# ProPrj_VI_sense_2025-01-02.net
KiCad netlist of a schematic drawn in EasyEDA Pro
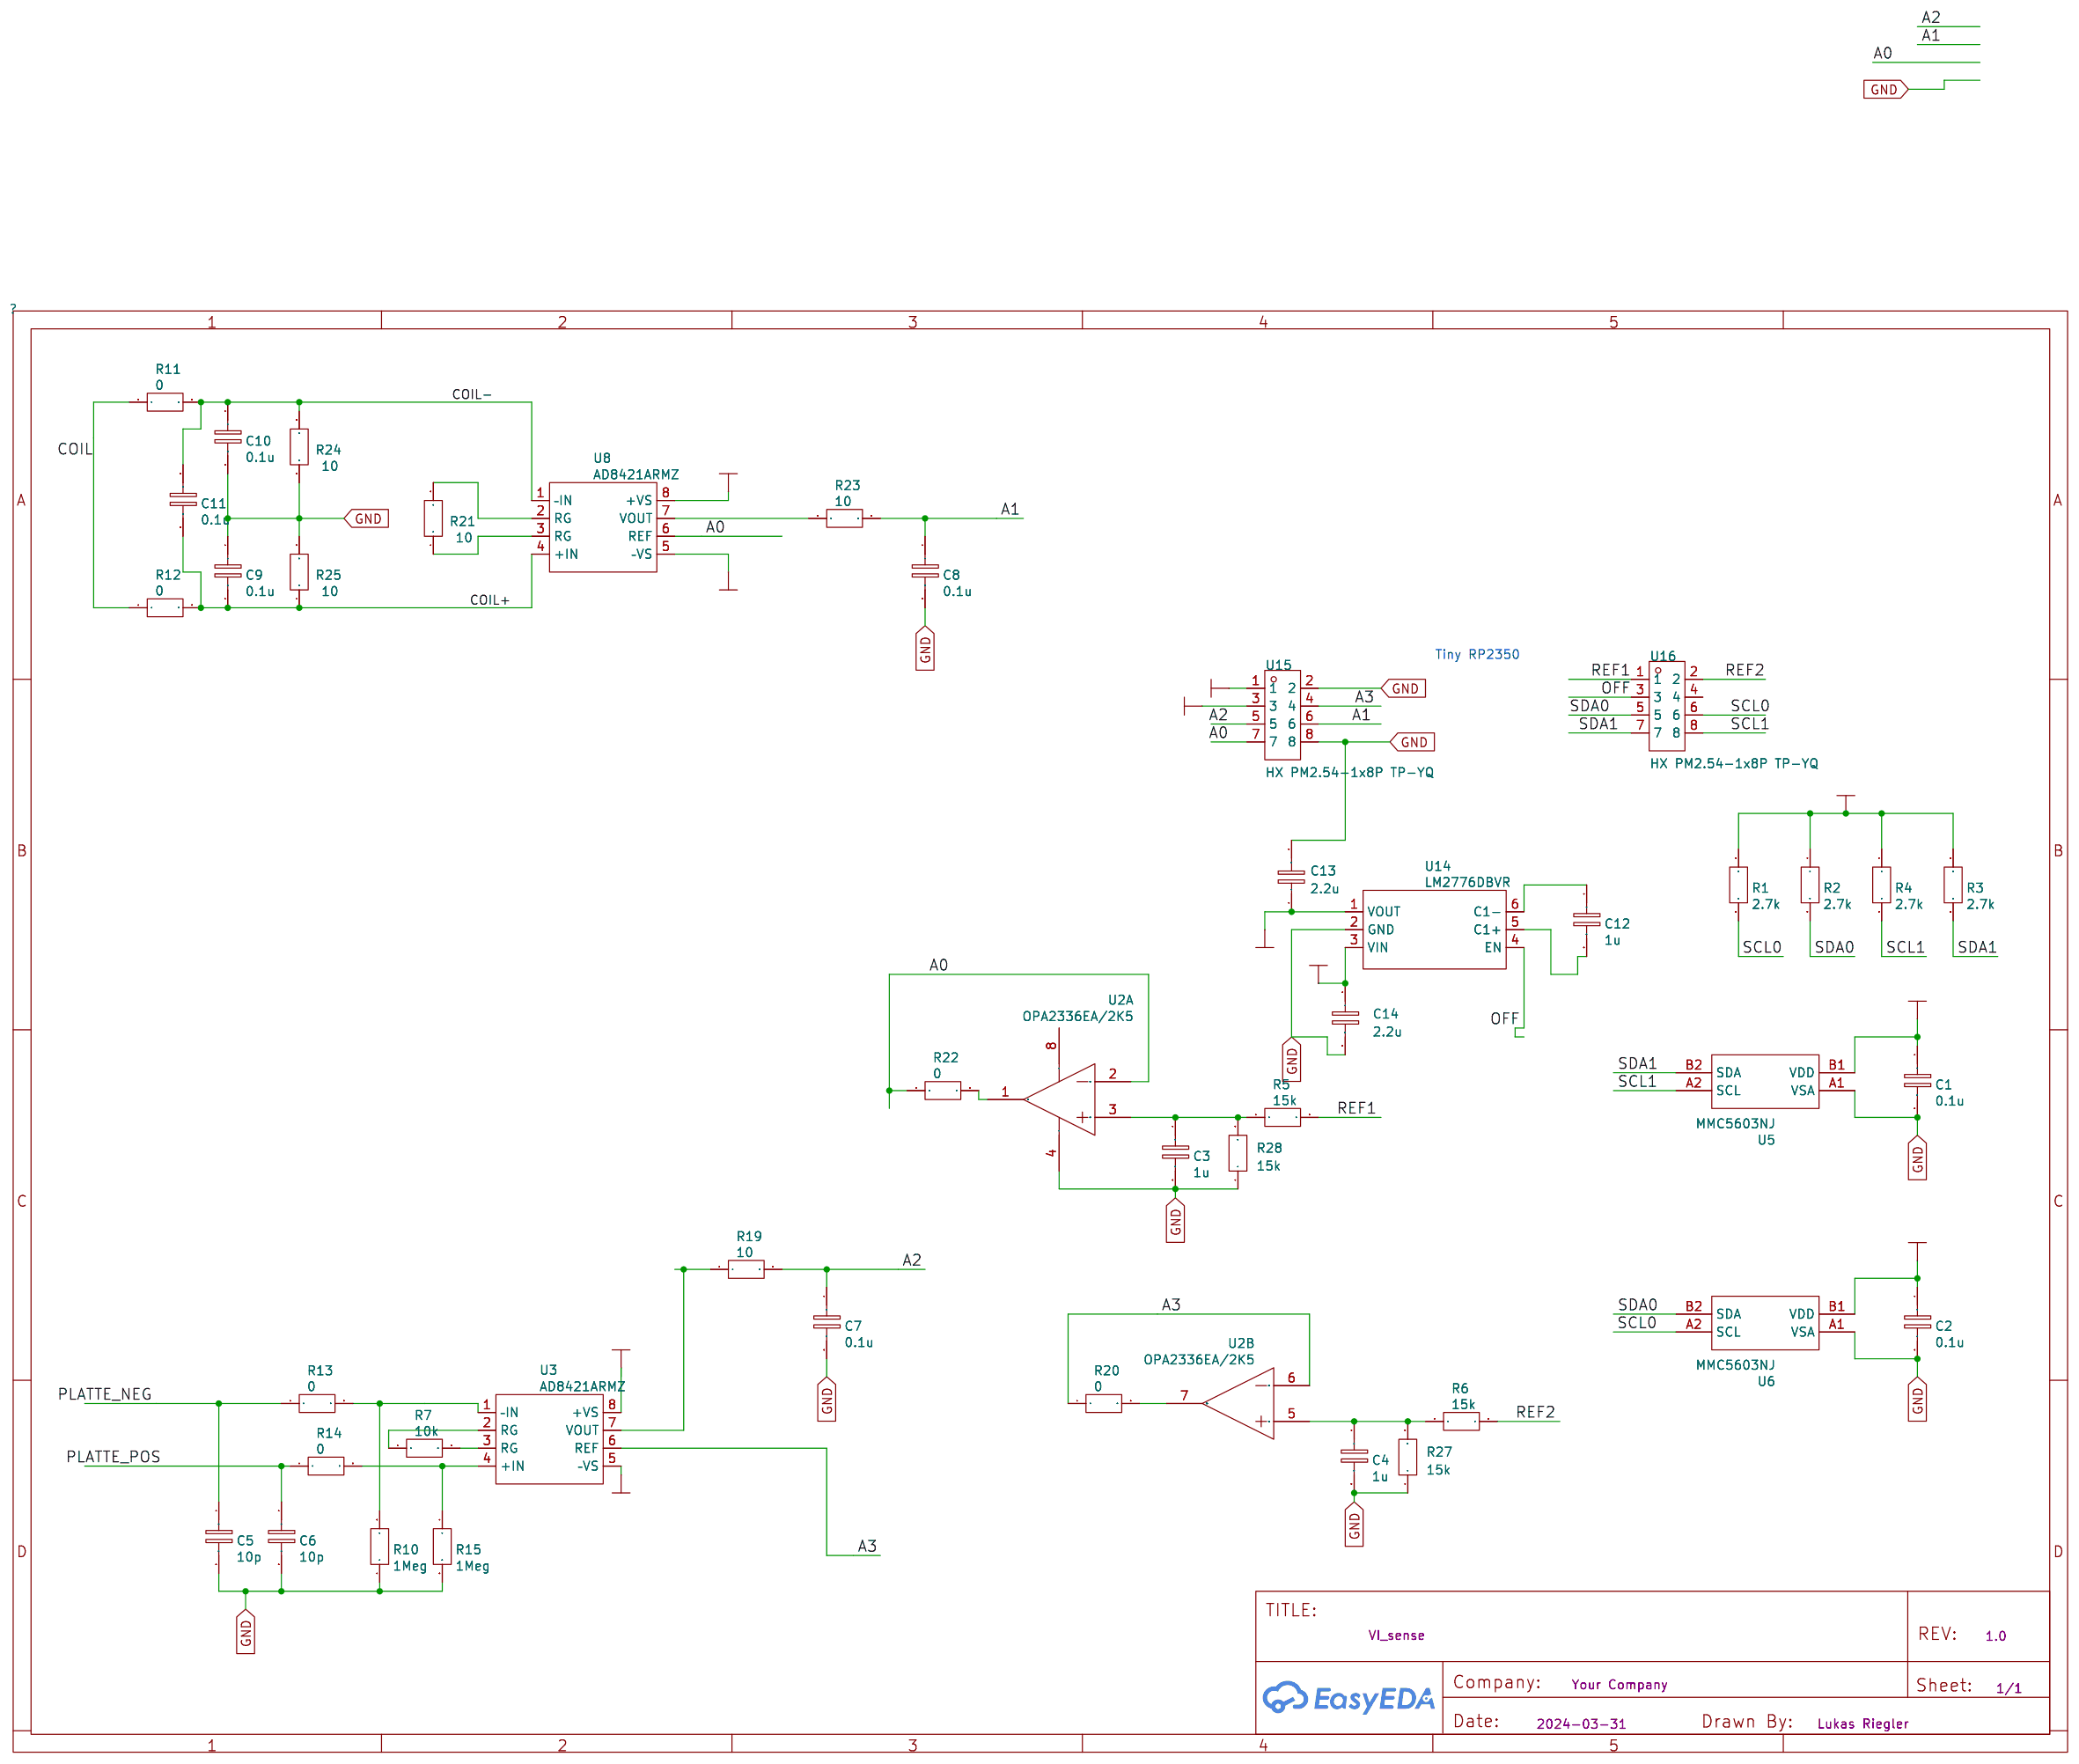
[diagram p0: schematic sheet]

(export (version "E")
  (design (tool "Eeschema 10.0.6"))
  (components
    (comp (ref "C1")
      (value "0.1u")
      (footprint "easyedapro:C0603")
      (libsource (lib "easyedapro") (part "0.1u"))
    )
    (comp (ref "C2")
      (value "0.1u")
      (footprint "easyedapro:C0603")
      (libsource (lib "easyedapro") (part "0.1u"))
    )
    (comp (ref "C3") (value "1u") (footprint "easyedapro:C0603") (libsource (lib "easyedapro") (part "1u")))
    (comp (ref "C4") (value "1u") (footprint "easyedapro:C0603") (libsource (lib "easyedapro") (part "1u")))
    (comp (ref "C5") (value "10p") (footprint "easyedapro:C0603") (libsource (lib "easyedapro") (part "10p")))
    (comp (ref "C6") (value "10p") (footprint "easyedapro:C0603") (libsource (lib "easyedapro") (part "10p")))
    (comp (ref "C7")
      (value "0.1u")
      (footprint "easyedapro:C0603")
      (libsource (lib "easyedapro") (part "0.1u"))
    )
    (comp (ref "C8")
      (value "0.1u")
      (footprint "easyedapro:C0603")
      (libsource (lib "easyedapro") (part "0.1u"))
    )
    (comp (ref "C9")
      (value "0.1u")
      (footprint "easyedapro:C0603")
      (libsource (lib "easyedapro") (part "0.1u"))
    )
    (comp (ref "C10")
      (value "0.1u")
      (footprint "easyedapro:C0603")
      (libsource (lib "easyedapro") (part "0.1u"))
    )
    (comp (ref "C11")
      (value "0.1u")
      (footprint "easyedapro:C0603")
      (libsource (lib "easyedapro") (part "0.1u"))
    )
    (comp (ref "C12")
      (value "1u")
      (footprint "easyedapro:C0603")
      (libsource (lib "easyedapro") (part "0.1u"))
    )
    (comp (ref "C13")
      (value "2.2u")
      (footprint "easyedapro:C0603")
      (libsource (lib "easyedapro") (part "0.1u"))
    )
    (comp (ref "C14")
      (value "2.2u")
      (footprint "easyedapro:C0603")
      (libsource (lib "easyedapro") (part "0.1u"))
    )
    (comp (ref "R1")
      (value "2.7k")
      (footprint "easyedapro:R0603")
      (libsource (lib "easyedapro") (part "2.7k"))
    )
    (comp (ref "R2")
      (value "2.7k")
      (footprint "easyedapro:R0603")
      (libsource (lib "easyedapro") (part "2.7k"))
    )
    (comp (ref "R3")
      (value "2.7k")
      (footprint "easyedapro:R0603")
      (libsource (lib "easyedapro") (part "2.7k"))
    )
    (comp (ref "R4")
      (value "2.7k")
      (footprint "easyedapro:R0603")
      (libsource (lib "easyedapro") (part "2.7k"))
    )
    (comp (ref "R5") (value "15k") (footprint "easyedapro:R0603") (libsource (lib "easyedapro") (part "15k")))
    (comp (ref "R6") (value "15k") (footprint "easyedapro:R0603") (libsource (lib "easyedapro") (part "15k")))
    (comp (ref "R7") (value "10k") (footprint "easyedapro:R0603") (libsource (lib "easyedapro") (part "10k")))
    (comp (ref "R10")
      (value "1Meg")
      (footprint "easyedapro:R0603")
      (libsource (lib "easyedapro") (part "1Meg"))
    )
    (comp (ref "R11") (value "0") (footprint "easyedapro:R0603") (libsource (lib "easyedapro") (part "0")))
    (comp (ref "R12") (value "0") (footprint "easyedapro:R0603") (libsource (lib "easyedapro") (part "0")))
    (comp (ref "R13") (value "0") (footprint "easyedapro:R0603") (libsource (lib "easyedapro") (part "0")))
    (comp (ref "R14") (value "0") (footprint "easyedapro:R0603") (libsource (lib "easyedapro") (part "0")))
    (comp (ref "R15")
      (value "1Meg")
      (footprint "easyedapro:R0603")
      (libsource (lib "easyedapro") (part "1Meg"))
    )
    (comp (ref "R19") (value "10") (footprint "easyedapro:R0603") (libsource (lib "easyedapro") (part "10")))
    (comp (ref "R20") (value "0") (footprint "easyedapro:R0603") (libsource (lib "easyedapro") (part "0")))
    (comp (ref "R21") (value "10") (footprint "easyedapro:R0603") (libsource (lib "easyedapro") (part "10")))
    (comp (ref "R22") (value "0") (footprint "easyedapro:R0603") (libsource (lib "easyedapro") (part "0")))
    (comp (ref "R23") (value "10") (footprint "easyedapro:R0603") (libsource (lib "easyedapro") (part "10")))
    (comp (ref "R24") (value "10") (footprint "easyedapro:R0603") (libsource (lib "easyedapro") (part "10")))
    (comp (ref "R25") (value "10") (footprint "easyedapro:R0603") (libsource (lib "easyedapro") (part "10")))
    (comp (ref "R27")
      (value "15k")
      (footprint "easyedapro:R0603")
      (libsource (lib "easyedapro") (part "15k"))
    )
    (comp (ref "R28")
      (value "15k")
      (footprint "easyedapro:R0603")
      (libsource (lib "easyedapro") (part "15k"))
    )
    (comp (ref "U2")
      (value "OPA2336EA/2K5")
      (footprint "easyedapro:VSSOP-8_L3.0-W3.0-P0.65-LS4.9-BL")
      (fields (field (name "Manufacturer") "TI(德州仪器)"))
      (libsource (lib "easyedapro") (part "OPA2336EA/2K5"))
    )
    (comp (ref "U3")
      (value "AD8421ARMZ")
      (footprint "easyedapro:MSOP-8_L3.0-W3.0-P0.65-LS4.9-BL")
      (fields (field (name "Manufacturer") "ADI(亚德诺)"))
      (libsource (lib "easyedapro") (part "AD8421ARMZ"))
    )
    (comp (ref "U5")
      (value "MMC5603NJ")
      (footprint "easyedapro:FLIPCHIP-4_L0.8-W0.8-R2-C2-P0.40-TL")
      (fields (field (name "Manufacturer") "MEMSIC(美新)"))
      (libsource (lib "easyedapro") (part "MMC5603NJ"))
    )
    (comp (ref "U6")
      (value "MMC5603NJ")
      (footprint "easyedapro:FLIPCHIP-4_L0.8-W0.8-R2-C2-P0.40-TL")
      (fields (field (name "Manufacturer") "MEMSIC(美新)"))
      (libsource (lib "easyedapro") (part "MMC5603NJ"))
    )
    (comp (ref "U8")
      (value "AD8421ARMZ")
      (footprint "easyedapro:MSOP-8_L3.0-W3.0-P0.65-LS4.9-BL")
      (fields (field (name "Manufacturer") "ADI(亚德诺)"))
      (libsource (lib "easyedapro") (part "AD8421ARMZ"))
    )
    (comp (ref "U14")
      (value "LM2776DBVR")
      (footprint "easyedapro:SOT-23-6_L2.9-W1.6-P0.95-LS2.8-BR")
      (fields (field (name "Manufacturer") "TI(德州仪器)"))
      (libsource (lib "easyedapro") (part "LM2776DBVR"))
    )
    (comp (ref "U15")
      (value "HX PM2.54-1x8P TP-YQ")
      (footprint "easyedapro:HDR-SMD_8P-P2.54-V-M-LS4.8_XKB_R1")
      (fields (field (name "Manufacturer") "hanxia(韩下)"))
      (libsource (lib "easyedapro") (part "HX PM2.54-1X8P TP-YQ"))
    )
    (comp (ref "U16")
      (value "HX PM2.54-1x8P TP-YQ")
      (footprint "easyedapro:HDR-SMD_8P-P2.54-V-M-LS4.8_XKB_R1")
      (fields (field (name "Manufacturer") "hanxia(韩下)"))
      (libsource (lib "easyedapro") (part "HX PM2.54-1X8P TP-YQ"))
    )
  )
  (nets
    (net (code "1") (name "+3.3V") (class "Default")
      (node (ref "C1") (pin "1") (pinfunction "1_1") (pintype "unspecified"))
      (node (ref "C2") (pin "1") (pinfunction "1_1") (pintype "unspecified"))
      (node (ref "R1") (pin "1") (pinfunction "1_1") (pintype "unspecified"))
      (node (ref "R2") (pin "1") (pinfunction "1_1") (pintype "unspecified"))
      (node (ref "R3") (pin "1") (pinfunction "1_1") (pintype "unspecified"))
      (node (ref "R4") (pin "1") (pinfunction "1_1") (pintype "unspecified"))
      (node (ref "U15") (pin "3") (pinfunction "3_3") (pintype "unspecified"))
      (node (ref "U5") (pin "B1") (pinfunction "VDD_B1") (pintype "unspecified"))
      (node (ref "U6") (pin "B1") (pinfunction "VDD_B1") (pintype "unspecified"))
    )
    (net (code "2") (name "+5V") (class "Default")
      (node (ref "C14") (pin "1") (pinfunction "1_1") (pintype "unspecified"))
      (node (ref "U14") (pin "3") (pinfunction "VIN_3") (pintype "unspecified"))
      (node (ref "U15") (pin "1") (pinfunction "1_1") (pintype "unspecified"))
      (node (ref "U3") (pin "8") (pinfunction "+VS_8") (pintype "unspecified"))
      (node (ref "U8") (pin "8") (pinfunction "+VS_8") (pintype "unspecified"))
    )
    (net (code "3") (name "-5V") (class "Default")
      (node (ref "C13") (pin "1") (pinfunction "1_1") (pintype "unspecified"))
      (node (ref "U14") (pin "1") (pinfunction "VOUT_1") (pintype "unspecified"))
      (node (ref "U3") (pin "5") (pinfunction "–VS_5") (pintype "unspecified"))
      (node (ref "U8") (pin "5") (pinfunction "–VS_5") (pintype "unspecified"))
    )
    (net (code "4") (name "/A0") (class "Default")
      (node (ref "R22") (pin "1") (pinfunction "1_1") (pintype "unspecified"))
      (node (ref "U15") (pin "7") (pinfunction "7_7") (pintype "unspecified"))
      (node (ref "U2") (pin "2") (pinfunction "IN_A-_2") (pintype "unspecified"))
      (node (ref "U8") (pin "6") (pinfunction "REF_6") (pintype "unspecified"))
    )
    (net (code "5") (name "/A1") (class "Default")
      (node (ref "C8") (pin "1") (pinfunction "1_1") (pintype "unspecified"))
      (node (ref "R23") (pin "2") (pinfunction "2_2") (pintype "unspecified"))
      (node (ref "U15") (pin "6") (pinfunction "6_6") (pintype "unspecified"))
    )
    (net (code "6") (name "/A2") (class "Default")
      (node (ref "C7") (pin "1") (pinfunction "1_1") (pintype "unspecified"))
      (node (ref "R19") (pin "2") (pinfunction "2_2") (pintype "unspecified"))
      (node (ref "U15") (pin "5") (pinfunction "5_5") (pintype "unspecified"))
    )
    (net (code "7") (name "/A3") (class "Default")
      (node (ref "R20") (pin "1") (pinfunction "1_1") (pintype "unspecified"))
      (node (ref "U15") (pin "4") (pinfunction "4_4") (pintype "unspecified"))
      (node (ref "U2") (pin "6") (pinfunction "IN_B-_6") (pintype "unspecified"))
      (node (ref "U3") (pin "6") (pinfunction "REF_6") (pintype "unspecified"))
    )
    (net (code "8") (name "/COIL") (class "Default")
      (node (ref "R11") (pin "1") (pinfunction "1_1") (pintype "unspecified"))
      (node (ref "R12") (pin "1") (pinfunction "1_1") (pintype "unspecified"))
    )
    (net (code "9") (name "/COIL+") (class "Default")
      (node (ref "C11") (pin "2") (pinfunction "2_2") (pintype "unspecified"))
      (node (ref "C9") (pin "2") (pinfunction "2_2") (pintype "unspecified"))
      (node (ref "R12") (pin "2") (pinfunction "2_2") (pintype "unspecified"))
      (node (ref "R25") (pin "1") (pinfunction "1_1") (pintype "unspecified"))
      (node (ref "U8") (pin "4") (pinfunction "+IN_4") (pintype "unspecified"))
    )
    (net (code "10") (name "/COIL-") (class "Default")
      (node (ref "C10") (pin "1") (pinfunction "1_1") (pintype "unspecified"))
      (node (ref "C11") (pin "1") (pinfunction "1_1") (pintype "unspecified"))
      (node (ref "R11") (pin "2") (pinfunction "2_2") (pintype "unspecified"))
      (node (ref "R24") (pin "2") (pinfunction "2_2") (pintype "unspecified"))
      (node (ref "U8") (pin "1") (pinfunction "–IN_1") (pintype "unspecified"))
    )
    (net (code "11") (name "/OFF") (class "Default")
      (node (ref "U14") (pin "4") (pinfunction "EN_4") (pintype "unspecified"))
      (node (ref "U16") (pin "3") (pinfunction "3_3") (pintype "unspecified"))
    )
    (net (code "12") (name "/PLATTE_NEG") (class "Default")
      (node (ref "C5") (pin "1") (pinfunction "1_1") (pintype "unspecified"))
      (node (ref "R13") (pin "1") (pinfunction "1_1") (pintype "unspecified"))
    )
    (net (code "13") (name "/PLATTE_POS") (class "Default")
      (node (ref "C6") (pin "1") (pinfunction "1_1") (pintype "unspecified"))
      (node (ref "R14") (pin "1") (pinfunction "1_1") (pintype "unspecified"))
    )
    (net (code "14") (name "/REF1") (class "Default")
      (node (ref "R5") (pin "2") (pinfunction "2_2") (pintype "unspecified"))
      (node (ref "U16") (pin "1") (pinfunction "1_1") (pintype "unspecified"))
    )
    (net (code "15") (name "/REF2") (class "Default")
      (node (ref "R6") (pin "2") (pinfunction "2_2") (pintype "unspecified"))
      (node (ref "U16") (pin "2") (pinfunction "2_2") (pintype "unspecified"))
    )
    (net (code "16") (name "/SCL0") (class "Default")
      (node (ref "R1") (pin "2") (pinfunction "2_2") (pintype "unspecified"))
      (node (ref "U16") (pin "6") (pinfunction "6_6") (pintype "unspecified"))
      (node (ref "U6") (pin "A2") (pinfunction "SCL_A2") (pintype "unspecified"))
    )
    (net (code "17") (name "/SCL1") (class "Default")
      (node (ref "R4") (pin "2") (pinfunction "2_2") (pintype "unspecified"))
      (node (ref "U16") (pin "8") (pinfunction "8_8") (pintype "unspecified"))
      (node (ref "U5") (pin "A2") (pinfunction "SCL_A2") (pintype "unspecified"))
    )
    (net (code "18") (name "/SDA0") (class "Default")
      (node (ref "R2") (pin "2") (pinfunction "2_2") (pintype "unspecified"))
      (node (ref "U16") (pin "5") (pinfunction "5_5") (pintype "unspecified"))
      (node (ref "U6") (pin "B2") (pinfunction "SDA_B2") (pintype "unspecified"))
    )
    (net (code "19") (name "/SDA1") (class "Default")
      (node (ref "R3") (pin "2") (pinfunction "2_2") (pintype "unspecified"))
      (node (ref "U16") (pin "7") (pinfunction "7_7") (pintype "unspecified"))
      (node (ref "U5") (pin "B2") (pinfunction "SDA_B2") (pintype "unspecified"))
    )
    (net (code "20") (name "GND") (class "Default")
      (node (ref "C1") (pin "2") (pinfunction "2_2") (pintype "unspecified"))
      (node (ref "C10") (pin "2") (pinfunction "2_2") (pintype "unspecified"))
      (node (ref "C13") (pin "2") (pinfunction "2_2") (pintype "unspecified"))
      (node (ref "C14") (pin "2") (pinfunction "2_2") (pintype "unspecified"))
      (node (ref "C2") (pin "2") (pinfunction "2_2") (pintype "unspecified"))
      (node (ref "C3") (pin "2") (pinfunction "2_2") (pintype "unspecified"))
      (node (ref "C4") (pin "2") (pinfunction "2_2") (pintype "unspecified"))
      (node (ref "C5") (pin "2") (pinfunction "2_2") (pintype "unspecified"))
      (node (ref "C6") (pin "2") (pinfunction "2_2") (pintype "unspecified"))
      (node (ref "C7") (pin "2") (pinfunction "2_2") (pintype "unspecified"))
      (node (ref "C8") (pin "2") (pinfunction "2_2") (pintype "unspecified"))
      (node (ref "C9") (pin "1") (pinfunction "1_1") (pintype "unspecified"))
      (node (ref "R10") (pin "1") (pinfunction "1_1") (pintype "unspecified"))
      (node (ref "R15") (pin "2") (pinfunction "2_2") (pintype "unspecified"))
      (node (ref "R24") (pin "1") (pinfunction "1_1") (pintype "unspecified"))
      (node (ref "R25") (pin "2") (pinfunction "2_2") (pintype "unspecified"))
      (node (ref "R27") (pin "1") (pinfunction "1_1") (pintype "unspecified"))
      (node (ref "R28") (pin "1") (pinfunction "1_1") (pintype "unspecified"))
      (node (ref "U14") (pin "2") (pinfunction "GND_2") (pintype "unspecified"))
      (node (ref "U15") (pin "2") (pinfunction "2_2") (pintype "unspecified"))
      (node (ref "U15") (pin "8") (pinfunction "8_8") (pintype "unspecified"))
      (node (ref "U2") (pin "4") (pinfunction "V-_4") (pintype "unspecified"))
      (node (ref "U5") (pin "A1") (pinfunction "VSA_A1") (pintype "unspecified"))
      (node (ref "U6") (pin "A1") (pinfunction "VSA_A1") (pintype "unspecified"))
    )
    (net (code "21") (name "Net-(R7-Pad1)") (class "Default")
      (node (ref "R7") (pin "1") (pinfunction "1_1") (pintype "unspecified"))
      (node (ref "U3") (pin "2") (pinfunction "RG_2") (pintype "unspecified"))
    )
    (net (code "22") (name "Net-(R7-Pad2)") (class "Default")
      (node (ref "R7") (pin "2") (pinfunction "2_2") (pintype "unspecified"))
      (node (ref "U3") (pin "3") (pinfunction "RG_3") (pintype "unspecified"))
    )
    (net (code "23") (name "Net-(R21-Pad1)") (class "Default")
      (node (ref "R21") (pin "1") (pinfunction "1_1") (pintype "unspecified"))
      (node (ref "U8") (pin "3") (pinfunction "RG_3") (pintype "unspecified"))
    )
    (net (code "24") (name "Net-(R21-Pad2)") (class "Default")
      (node (ref "R21") (pin "2") (pinfunction "2_2") (pintype "unspecified"))
      (node (ref "U8") (pin "2") (pinfunction "RG_2") (pintype "unspecified"))
    )
    (net (code "25") (name "Net-(U2A-IN_A+)") (class "Default")
      (node (ref "C3") (pin "1") (pinfunction "1_1") (pintype "unspecified"))
      (node (ref "R28") (pin "2") (pinfunction "2_2") (pintype "unspecified"))
      (node (ref "R5") (pin "1") (pinfunction "1_1") (pintype "unspecified"))
      (node (ref "U2") (pin "3") (pinfunction "IN_A+_3") (pintype "unspecified"))
    )
    (net (code "26") (name "Net-(U2A-OUT_A)") (class "Default")
      (node (ref "R22") (pin "2") (pinfunction "2_2") (pintype "unspecified"))
      (node (ref "U2") (pin "1") (pinfunction "OUT_A_1") (pintype "output"))
    )
    (net (code "27") (name "Net-(U2B-IN_B+)") (class "Default")
      (node (ref "C4") (pin "1") (pinfunction "1_1") (pintype "unspecified"))
      (node (ref "R27") (pin "2") (pinfunction "2_2") (pintype "unspecified"))
      (node (ref "R6") (pin "1") (pinfunction "1_1") (pintype "unspecified"))
      (node (ref "U2") (pin "5") (pinfunction "IN_B+_5") (pintype "unspecified"))
    )
    (net (code "28") (name "Net-(U2B-OUT_B)") (class "Default")
      (node (ref "R20") (pin "2") (pinfunction "2_2") (pintype "unspecified"))
      (node (ref "U2") (pin "7") (pinfunction "OUT_B_7") (pintype "output"))
    )
    (net (code "29") (name "Net-(U3-+IN)") (class "Default")
      (node (ref "R14") (pin "2") (pinfunction "2_2") (pintype "unspecified"))
      (node (ref "R15") (pin "1") (pinfunction "1_1") (pintype "unspecified"))
      (node (ref "U3") (pin "4") (pinfunction "+IN_4") (pintype "unspecified"))
    )
    (net (code "30") (name "Net-(U3-VOUT)") (class "Default")
      (node (ref "R19") (pin "1") (pinfunction "1_1") (pintype "unspecified"))
      (node (ref "U3") (pin "7") (pinfunction "VOUT_7") (pintype "unspecified"))
    )
    (net (code "31") (name "Net-(U3-–IN)") (class "Default")
      (node (ref "R10") (pin "2") (pinfunction "2_2") (pintype "unspecified"))
      (node (ref "R13") (pin "2") (pinfunction "2_2") (pintype "unspecified"))
      (node (ref "U3") (pin "1") (pinfunction "–IN_1") (pintype "unspecified"))
    )
    (net (code "32") (name "Net-(U8-VOUT)") (class "Default")
      (node (ref "R23") (pin "1") (pinfunction "1_1") (pintype "unspecified"))
      (node (ref "U8") (pin "7") (pinfunction "VOUT_7") (pintype "unspecified"))
    )
    (net (code "33") (name "Net-(U14-C1+)") (class "Default")
      (node (ref "C12") (pin "2") (pinfunction "2_2") (pintype "unspecified"))
      (node (ref "U14") (pin "5") (pinfunction "C1+_5") (pintype "unspecified"))
    )
    (net (code "34") (name "Net-(U14-C1-)") (class "Default")
      (node (ref "C12") (pin "1") (pinfunction "1_1") (pintype "unspecified"))
      (node (ref "U14") (pin "6") (pinfunction "C1-_6") (pintype "unspecified"))
    )
    (net (code "35") (name "unconnected-(U2A-V+-Pad8)") (class "Default")
      (node (ref "U2") (pin "8") (pinfunction "V+_8") (pintype "unspecified"))
    )
    (net (code "36") (name "unconnected-(U16-Pad4)") (class "Default")
      (node (ref "U16") (pin "4") (pinfunction "4_4") (pintype "unspecified"))
    )
  )
)
